# ProgSwitch.net
KiCad netlist of a schematic drawn in EAGLE
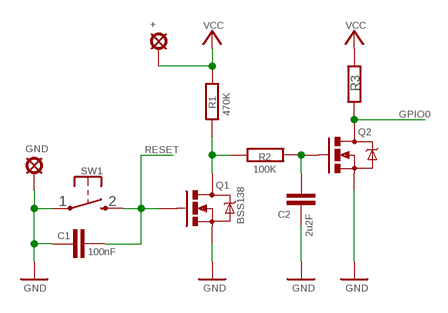
[diagram p0: schematic, sheet 1]

(export (version "E")
  (design (tool "Eeschema 10.0.6"))
  (components
    (comp (ref "+")
      (value "LSP10")
      (footprint "eagle-import:LSP10")
      (libsource (lib "eagle-import") (part "LSP10"))
    )
    (comp (ref "C1")
      (value "100nF")
      (footprint "eagle-import:C025-024X044")
      (libsource (lib "eagle-import") (part "C-EU025-024X044"))
    )
    (comp (ref "C2")
      (value "2u2F")
      (footprint "eagle-import:C025-024X044")
      (libsource (lib "eagle-import") (part "C-EU025-024X044"))
    )
    (comp (ref "GND")
      (value "LSP10")
      (footprint "eagle-import:LSP10")
      (libsource (lib "eagle-import") (part "LSP10"))
    )
    (comp (ref "Q1")
      (value "BSS138")
      (footprint "eagle-import:SOT23-3")
      (libsource (lib "eagle-import") (part "MOSFET-NCHANNELAO3404A"))
    )
    (comp (ref "Q2")
      (value "BSS138")
      (footprint "eagle-import:SOT23-3")
      (libsource (lib "eagle-import") (part "MOSFET-NCHANNELAO3404A"))
    )
    (comp (ref "R1")
      (value "470K")
      (footprint "eagle-import:R0805")
      (libsource (lib "eagle-import") (part "R-EU_R0805"))
    )
    (comp (ref "R2")
      (value "100K")
      (footprint "eagle-import:R0805")
      (libsource (lib "eagle-import") (part "R-EU_R0805"))
    )
    (comp (ref "R3")
      (value "R-EU_R0805")
      (footprint "eagle-import:R0805")
      (libsource (lib "eagle-import") (part "R-EU_R0805"))
    )
    (comp (ref "SW1")
      (value "KSS-2EG4430")
      (footprint "eagle-import:KSS-2EG4430")
      (libsource (lib "eagle-import") (part "KSS-2EG4430"))
    )
  )
  (nets
    (net (code "1") (name "/GPIO0") (class "Default")
      (node (ref "Q2") (pin "3") (pinfunction "D_3") (pintype "passive"))
      (node (ref "R3") (pin "2") (pinfunction "2_2") (pintype "passive"))
    )
    (net (code "2") (name "/RESET") (class "Default")
      (node (ref "C1") (pin "2") (pinfunction "2_2") (pintype "passive"))
      (node (ref "Q1") (pin "1") (pinfunction "G_1") (pintype "passive"))
      (node (ref "SW1") (pin "2") (pinfunction "S_2") (pintype "passive"))
    )
    (net (code "3") (name "GND") (class "Default")
      (node (ref "C1") (pin "1") (pinfunction "1_1") (pintype "passive"))
      (node (ref "C2") (pin "1") (pinfunction "1_1") (pintype "passive"))
      (node (ref "GND") (pin "MP") (pinfunction "MP_MP") (pintype "passive"))
      (node (ref "Q1") (pin "2") (pinfunction "S_2") (pintype "passive"))
      (node (ref "Q2") (pin "2") (pinfunction "S_2") (pintype "passive"))
      (node (ref "SW1") (pin "1") (pinfunction "P_1") (pintype "passive"))
    )
    (net (code "4") (name "Net-(Q1-D)") (class "Default")
      (node (ref "Q1") (pin "3") (pinfunction "D_3") (pintype "passive"))
      (node (ref "R1") (pin "1") (pinfunction "1_1") (pintype "passive"))
      (node (ref "R2") (pin "1") (pinfunction "1_1") (pintype "passive"))
    )
    (net (code "5") (name "Net-(Q2-G)") (class "Default")
      (node (ref "C2") (pin "2") (pinfunction "2_2") (pintype "passive"))
      (node (ref "Q2") (pin "1") (pinfunction "G_1") (pintype "passive"))
      (node (ref "R2") (pin "2") (pinfunction "2_2") (pintype "passive"))
    )
    (net (code "6") (name "VCC") (class "Default")
      (node (ref "+") (pin "MP") (pinfunction "MP_MP") (pintype "passive"))
      (node (ref "R1") (pin "2") (pinfunction "2_2") (pintype "passive"))
      (node (ref "R3") (pin "1") (pinfunction "1_1") (pintype "passive"))
    )
  )
)
